# MotorControl.net
KiCad netlist of a schematic drawn in Altium Designer
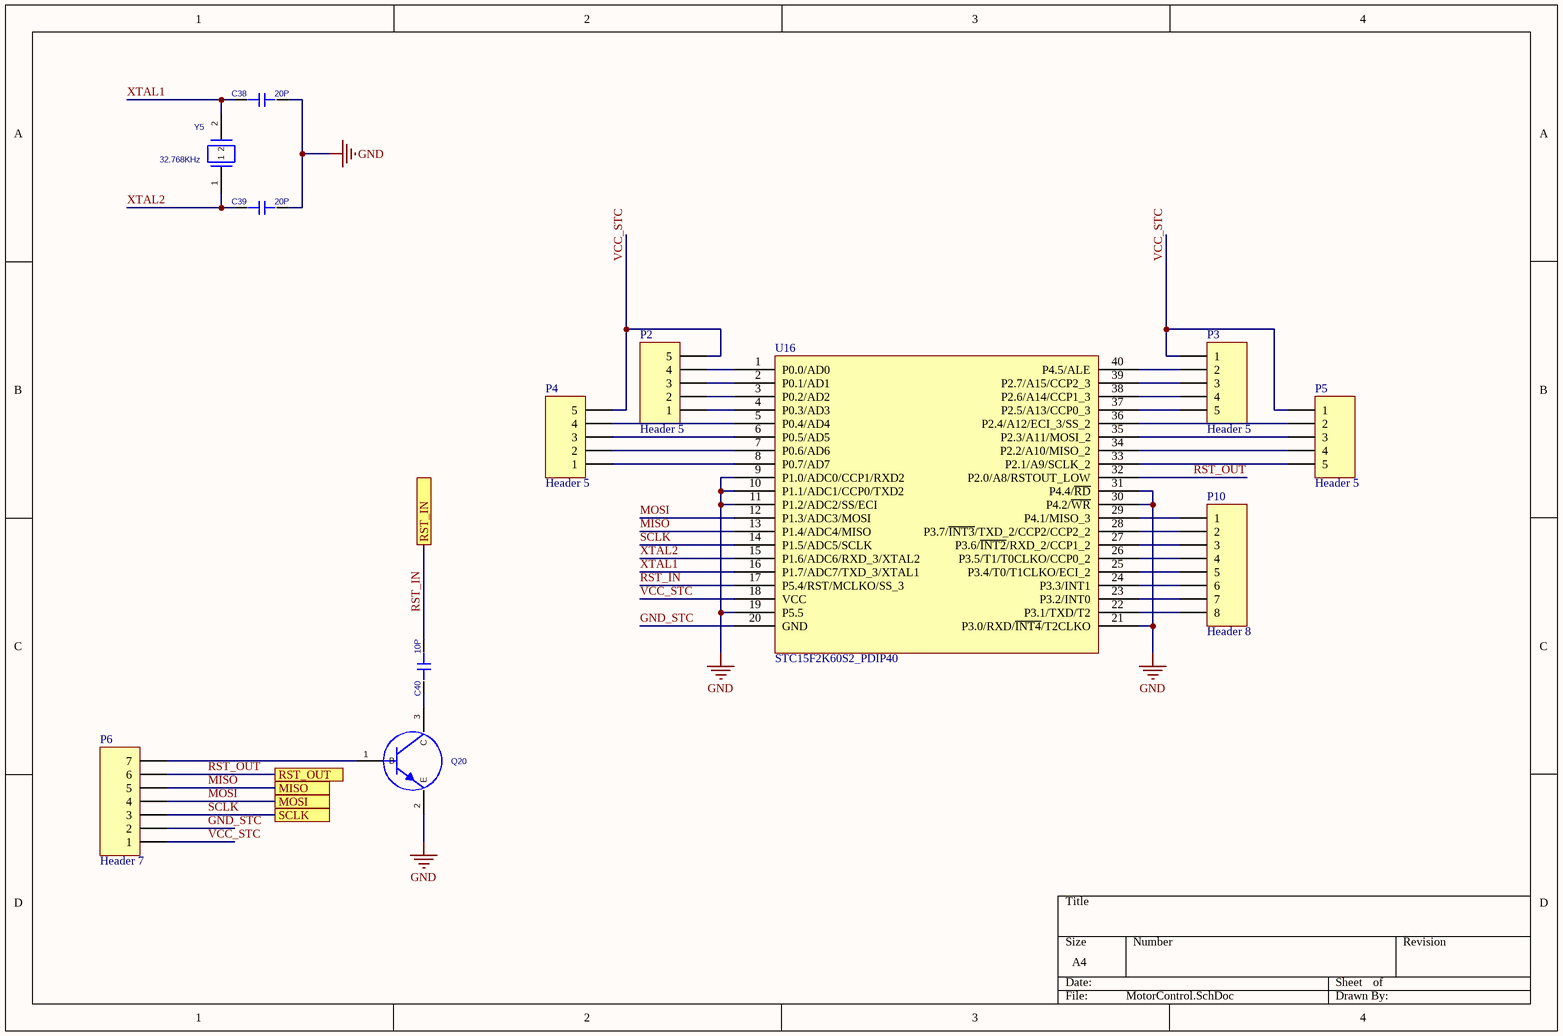
[diagram p0: MotorControl.SchDoc]

(export (version "E")
  (design (tool "Eeschema 10.0.6"))
  (components
    (comp (ref "C38")
      (value "20P")
      (footprint "CAP_0603_FIRE")
      (fields (field (name "Comment") "CAP_20P_0603_FIRE"))
      (libsource (lib "MINI-V3") (part "CAP_20P_0603_FIRE"))
    )
    (comp (ref "C39")
      (value "20P")
      (footprint "CAP_0603_FIRE")
      (fields (field (name "Comment") "CAP_20P_0603_FIRE"))
      (libsource (lib "MINI-V3") (part "CAP_20P_0603_FIRE"))
    )
    (comp (ref "C40")
      (value "10P")
      (footprint "RES_0603_FIRE")
      (description "0603")
      (fields (field (name "TOLERANCE") "+-5%") (field (name "Comment") "CAP_10P_0603_FIRE"))
      (libsource (lib "MINI-V3") (part "CAP_10P_0603_FIRE"))
    )
    (comp (ref "P2")
      (value "Header 5")
      (footprint "HDR1X5")
      (description "Header, 5-Pin")
      (fields (field (name "PUBLISHER") "Altium Limited"))
      (libsource (lib "") (part "Header 5_1"))
    )
    (comp (ref "P3")
      (value "Header 5")
      (footprint "HDR1X5")
      (description "Header, 5-Pin")
      (fields (field (name "PUBLISHER") "Altium Limited"))
      (libsource (lib "插针") (part "Header 5"))
    )
    (comp (ref "P4")
      (value "Header 5")
      (footprint "HDR1X5")
      (description "Header, 5-Pin")
      (fields (field (name "PUBLISHER") "Altium Limited"))
      (libsource (lib "") (part "Header 5_1"))
    )
    (comp (ref "P5")
      (value "Header 5")
      (footprint "HDR1X5")
      (description "Header, 5-Pin")
      (fields (field (name "PUBLISHER") "Altium Limited"))
      (libsource (lib "插针") (part "Header 5"))
    )
    (comp (ref "P6")
      (value "Header 7")
      (description "Header, 7-Pin")
      (fields (field (name "PUBLISHER") "Altium Limited"))
      (libsource (lib "插针") (part "Header 7"))
    )
    (comp (ref "P10")
      (value "Header 8")
      (footprint "HDR1X8")
      (description "Header, 8-Pin")
      (fields (field (name "PUBLISHER") "Altium Limited"))
      (libsource (lib "插针") (part "Header 8"))
    )
    (comp (ref "Q20")
      (value "8050")
      (footprint "SOT-23")
      (description "NPN")
      (libsource (lib "MINI-V3") (part "8050"))
    )
    (comp (ref "U16")
      (value "STC15F2K60S2_PDIP40")
      (footprint "DIP40")
      (libsource (lib "STCMCU") (part "STC15F2K60S2_PDIP40"))
    )
    (comp (ref "Y5")
      (value "32.768KHz")
      (footprint "3215")
      (description "CRYSTAL")
      (fields (field (name "Comment") "XTAL_32.768KHZ_3215"))
      (libsource (lib "MINI-V3") (part "XTAL_32.768KHZ_3215"))
    )
  )
  (nets
    (net (code "1") (name "/GND_STC") (class "Default")
      (node (ref "P6") (pin "2") (pinfunction "2_2") (pintype "passive"))
      (node (ref "U16") (pin "20") (pinfunction "GND_20") (pintype "passive"))
    )
    (net (code "2") (name "/MISO") (class "Default")
      (node (ref "P6") (pin "5") (pinfunction "5_5") (pintype "passive"))
      (node (ref "U16") (pin "13") (pinfunction "P1.4/ADC4/MISO_13") (pintype "passive"))
    )
    (net (code "3") (name "/MOSI") (class "Default")
      (node (ref "P6") (pin "4") (pinfunction "4_4") (pintype "passive"))
      (node (ref "U16") (pin "12") (pinfunction "P1.3/ADC3/MOSI_12") (pintype "passive"))
    )
    (net (code "4") (name "/RST_IN") (class "Default")
      (node (ref "C40") (pin "2") (pinfunction "2_2") (pintype "passive"))
      (node (ref "U16") (pin "17") (pinfunction "P5.4/RST/MCLKO/SS_3_17") (pintype "passive"))
    )
    (net (code "5") (name "/RST_OUT") (class "Default")
      (node (ref "P6") (pin "6") (pinfunction "6_6") (pintype "passive"))
      (node (ref "U16") (pin "32") (pinfunction "P2.0/A8/RSTOUT_LOW_32") (pintype "passive"))
    )
    (net (code "6") (name "/SCLK") (class "Default")
      (node (ref "P6") (pin "3") (pinfunction "3_3") (pintype "passive"))
      (node (ref "U16") (pin "14") (pinfunction "P1.5/ADC5/SCLK_14") (pintype "passive"))
    )
    (net (code "7") (name "/VCC_STC") (class "Default")
      (node (ref "P2") (pin "5") (pinfunction "5_5") (pintype "passive"))
      (node (ref "P3") (pin "1") (pinfunction "1_1") (pintype "passive"))
      (node (ref "P4") (pin "5") (pinfunction "5_5") (pintype "passive"))
      (node (ref "P5") (pin "1") (pinfunction "1_1") (pintype "passive"))
      (node (ref "P6") (pin "1") (pinfunction "1_1") (pintype "passive"))
      (node (ref "U16") (pin "18") (pinfunction "VCC_18") (pintype "passive"))
    )
    (net (code "8") (name "/XTAL1") (class "Default")
      (node (ref "C38") (pin "1") (pinfunction "1_1") (pintype "passive"))
      (node (ref "U16") (pin "16") (pinfunction "P1.7/ADC7/TXD_3/XTAL1_16") (pintype "passive"))
      (node (ref "Y5") (pin "2") (pinfunction "2_2") (pintype "passive"))
    )
    (net (code "9") (name "/XTAL2") (class "Default")
      (node (ref "C39") (pin "1") (pinfunction "1_1") (pintype "passive"))
      (node (ref "U16") (pin "15") (pinfunction "P1.6/ADC6/RXD_3/XTAL2_15") (pintype "passive"))
      (node (ref "Y5") (pin "1") (pinfunction "1_1") (pintype "passive"))
    )
    (net (code "10") (name "GND") (class "Default")
      (node (ref "C38") (pin "2") (pinfunction "2_2") (pintype "passive"))
      (node (ref "C39") (pin "2") (pinfunction "2_2") (pintype "passive"))
      (node (ref "Q20") (pin "2") (pinfunction "E_2") (pintype "passive"))
      (node (ref "U16") (pin "10") (pinfunction "P1.1/ADC1/CCP0/TXD2_10") (pintype "passive"))
      (node (ref "U16") (pin "11") (pinfunction "P1.2/ADC2/SS/ECI_11") (pintype "passive"))
      (node (ref "U16") (pin "19") (pinfunction "P5.5_19") (pintype "passive"))
      (node (ref "U16") (pin "21") (pinfunction "P3.0/RXD/~{INT4}/T2CLKO_21") (pintype "passive"))
      (node (ref "U16") (pin "30") (pinfunction "P4.2/~{WR}_30") (pintype "passive"))
      (node (ref "U16") (pin "31") (pinfunction "P4.4/~{RD}_31") (pintype "passive"))
      (node (ref "U16") (pin "9") (pinfunction "P1.0/ADC0/CCP1/RXD2_9") (pintype "passive"))
    )
    (net (code "11") (name "Net-(Q20-B)") (class "Default")
      (node (ref "P6") (pin "7") (pinfunction "7_7") (pintype "passive"))
      (node (ref "Q20") (pin "1") (pinfunction "B_1") (pintype "passive"))
    )
    (net (code "12") (name "Net-(Q20-C)") (class "Default")
      (node (ref "C40") (pin "1") (pinfunction "1_1") (pintype "passive"))
      (node (ref "Q20") (pin "3") (pinfunction "C_3") (pintype "passive"))
    )
    (net (code "13") (name "Net-(U16-P0.0{slash}AD0)") (class "Default")
      (node (ref "P2") (pin "4") (pinfunction "4_4") (pintype "passive"))
      (node (ref "U16") (pin "1") (pinfunction "P0.0/AD0_1") (pintype "passive"))
    )
    (net (code "14") (name "Net-(U16-P0.1{slash}AD1)") (class "Default")
      (node (ref "P2") (pin "3") (pinfunction "3_3") (pintype "passive"))
      (node (ref "U16") (pin "2") (pinfunction "P0.1/AD1_2") (pintype "passive"))
    )
    (net (code "15") (name "Net-(U16-P0.2{slash}AD2)") (class "Default")
      (node (ref "P2") (pin "2") (pinfunction "2_2") (pintype "passive"))
      (node (ref "U16") (pin "3") (pinfunction "P0.2/AD2_3") (pintype "passive"))
    )
    (net (code "16") (name "Net-(U16-P0.3{slash}AD3)") (class "Default")
      (node (ref "P2") (pin "1") (pinfunction "1_1") (pintype "passive"))
      (node (ref "U16") (pin "4") (pinfunction "P0.3/AD3_4") (pintype "passive"))
    )
    (net (code "17") (name "Net-(U16-P0.4{slash}AD4)") (class "Default")
      (node (ref "P4") (pin "4") (pinfunction "4_4") (pintype "passive"))
      (node (ref "U16") (pin "5") (pinfunction "P0.4/AD4_5") (pintype "passive"))
    )
    (net (code "18") (name "Net-(U16-P0.5{slash}AD5)") (class "Default")
      (node (ref "P4") (pin "3") (pinfunction "3_3") (pintype "passive"))
      (node (ref "U16") (pin "6") (pinfunction "P0.5/AD5_6") (pintype "passive"))
    )
    (net (code "19") (name "Net-(U16-P0.6{slash}AD6)") (class "Default")
      (node (ref "P4") (pin "2") (pinfunction "2_2") (pintype "passive"))
      (node (ref "U16") (pin "7") (pinfunction "P0.6/AD6_7") (pintype "passive"))
    )
    (net (code "20") (name "Net-(U16-P0.7{slash}AD7)") (class "Default")
      (node (ref "P4") (pin "1") (pinfunction "1_1") (pintype "passive"))
      (node (ref "U16") (pin "8") (pinfunction "P0.7/AD7_8") (pintype "passive"))
    )
    (net (code "21") (name "Net-(U16-P2.1{slash}A9{slash}SCLK_2)") (class "Default")
      (node (ref "P5") (pin "5") (pinfunction "5_5") (pintype "passive"))
      (node (ref "U16") (pin "33") (pinfunction "P2.1/A9/SCLK_2_33") (pintype "passive"))
    )
    (net (code "22") (name "Net-(U16-P2.2{slash}A10{slash}MISO_2)") (class "Default")
      (node (ref "P5") (pin "4") (pinfunction "4_4") (pintype "passive"))
      (node (ref "U16") (pin "34") (pinfunction "P2.2/A10/MISO_2_34") (pintype "passive"))
    )
    (net (code "23") (name "Net-(U16-P2.3{slash}A11{slash}MOSI_2)") (class "Default")
      (node (ref "P5") (pin "3") (pinfunction "3_3") (pintype "passive"))
      (node (ref "U16") (pin "35") (pinfunction "P2.3/A11/MOSI_2_35") (pintype "passive"))
    )
    (net (code "24") (name "Net-(U16-P2.4{slash}A12{slash}ECI_3{slash}SS_2)") (class "Default")
      (node (ref "P5") (pin "2") (pinfunction "2_2") (pintype "passive"))
      (node (ref "U16") (pin "36") (pinfunction "P2.4/A12/ECI_3/SS_2_36") (pintype "passive"))
    )
    (net (code "25") (name "Net-(U16-P2.5{slash}A13{slash}CCP0_3)") (class "Default")
      (node (ref "P3") (pin "5") (pinfunction "5_5") (pintype "passive"))
      (node (ref "U16") (pin "37") (pinfunction "P2.5/A13/CCP0_3_37") (pintype "passive"))
    )
    (net (code "26") (name "Net-(U16-P2.6{slash}A14{slash}CCP1_3)") (class "Default")
      (node (ref "P3") (pin "4") (pinfunction "4_4") (pintype "passive"))
      (node (ref "U16") (pin "38") (pinfunction "P2.6/A14/CCP1_3_38") (pintype "passive"))
    )
    (net (code "27") (name "Net-(U16-P2.7{slash}A15{slash}CCP2_3)") (class "Default")
      (node (ref "P3") (pin "3") (pinfunction "3_3") (pintype "passive"))
      (node (ref "U16") (pin "39") (pinfunction "P2.7/A15/CCP2_3_39") (pintype "passive"))
    )
    (net (code "28") (name "Net-(U16-P3.1{slash}TXD{slash}T2)") (class "Default")
      (node (ref "P10") (pin "8") (pinfunction "8_8") (pintype "passive"))
      (node (ref "U16") (pin "22") (pinfunction "P3.1/TXD/T2_22") (pintype "passive"))
    )
    (net (code "29") (name "Net-(U16-P3.2{slash}INT0)") (class "Default")
      (node (ref "P10") (pin "7") (pinfunction "7_7") (pintype "passive"))
      (node (ref "U16") (pin "23") (pinfunction "P3.2/INT0_23") (pintype "passive"))
    )
    (net (code "30") (name "Net-(U16-P3.3{slash}INT1)") (class "Default")
      (node (ref "P10") (pin "6") (pinfunction "6_6") (pintype "passive"))
      (node (ref "U16") (pin "24") (pinfunction "P3.3/INT1_24") (pintype "passive"))
    )
    (net (code "31") (name "Net-(U16-P3.4{slash}T0{slash}T1CLKO{slash}ECI_2)") (class "Default")
      (node (ref "P10") (pin "5") (pinfunction "5_5") (pintype "passive"))
      (node (ref "U16") (pin "25") (pinfunction "P3.4/T0/T1CLKO/ECI_2_25") (pintype "passive"))
    )
    (net (code "32") (name "Net-(U16-P3.5{slash}T1{slash}T0CLKO{slash}CCP0_2)") (class "Default")
      (node (ref "P10") (pin "4") (pinfunction "4_4") (pintype "passive"))
      (node (ref "U16") (pin "26") (pinfunction "P3.5/T1/T0CLKO/CCP0_2_26") (pintype "passive"))
    )
    (net (code "33") (name "Net-(U16-P3.6{slash}~{INT2}{slash}RXD_2{slash}CCP1_2)") (class "Default")
      (node (ref "P10") (pin "3") (pinfunction "3_3") (pintype "passive"))
      (node (ref "U16") (pin "27") (pinfunction "P3.6/~{INT2}/RXD_2/CCP1_2_27") (pintype "passive"))
    )
    (net (code "34") (name "Net-(U16-P3.7{slash}~{INT3}{slash}TXD_2{slash}CCP2{slash}CCP2_2)") (class "Default")
      (node (ref "P10") (pin "2") (pinfunction "2_2") (pintype "passive"))
      (node (ref "U16") (pin "28") (pinfunction "P3.7/~{INT3}/TXD_2/CCP2/CCP2_2_28") (pintype "passive"))
    )
    (net (code "35") (name "Net-(U16-P4.1{slash}MISO_3)") (class "Default")
      (node (ref "P10") (pin "1") (pinfunction "1_1") (pintype "passive"))
      (node (ref "U16") (pin "29") (pinfunction "P4.1/MISO_3_29") (pintype "passive"))
    )
    (net (code "36") (name "Net-(U16-P4.5{slash}ALE)") (class "Default")
      (node (ref "P3") (pin "2") (pinfunction "2_2") (pintype "passive"))
      (node (ref "U16") (pin "40") (pinfunction "P4.5/ALE_40") (pintype "passive"))
    )
  )
)
